# DDR-Memory.net
KiCad netlist of a schematic drawn in Altium Designer
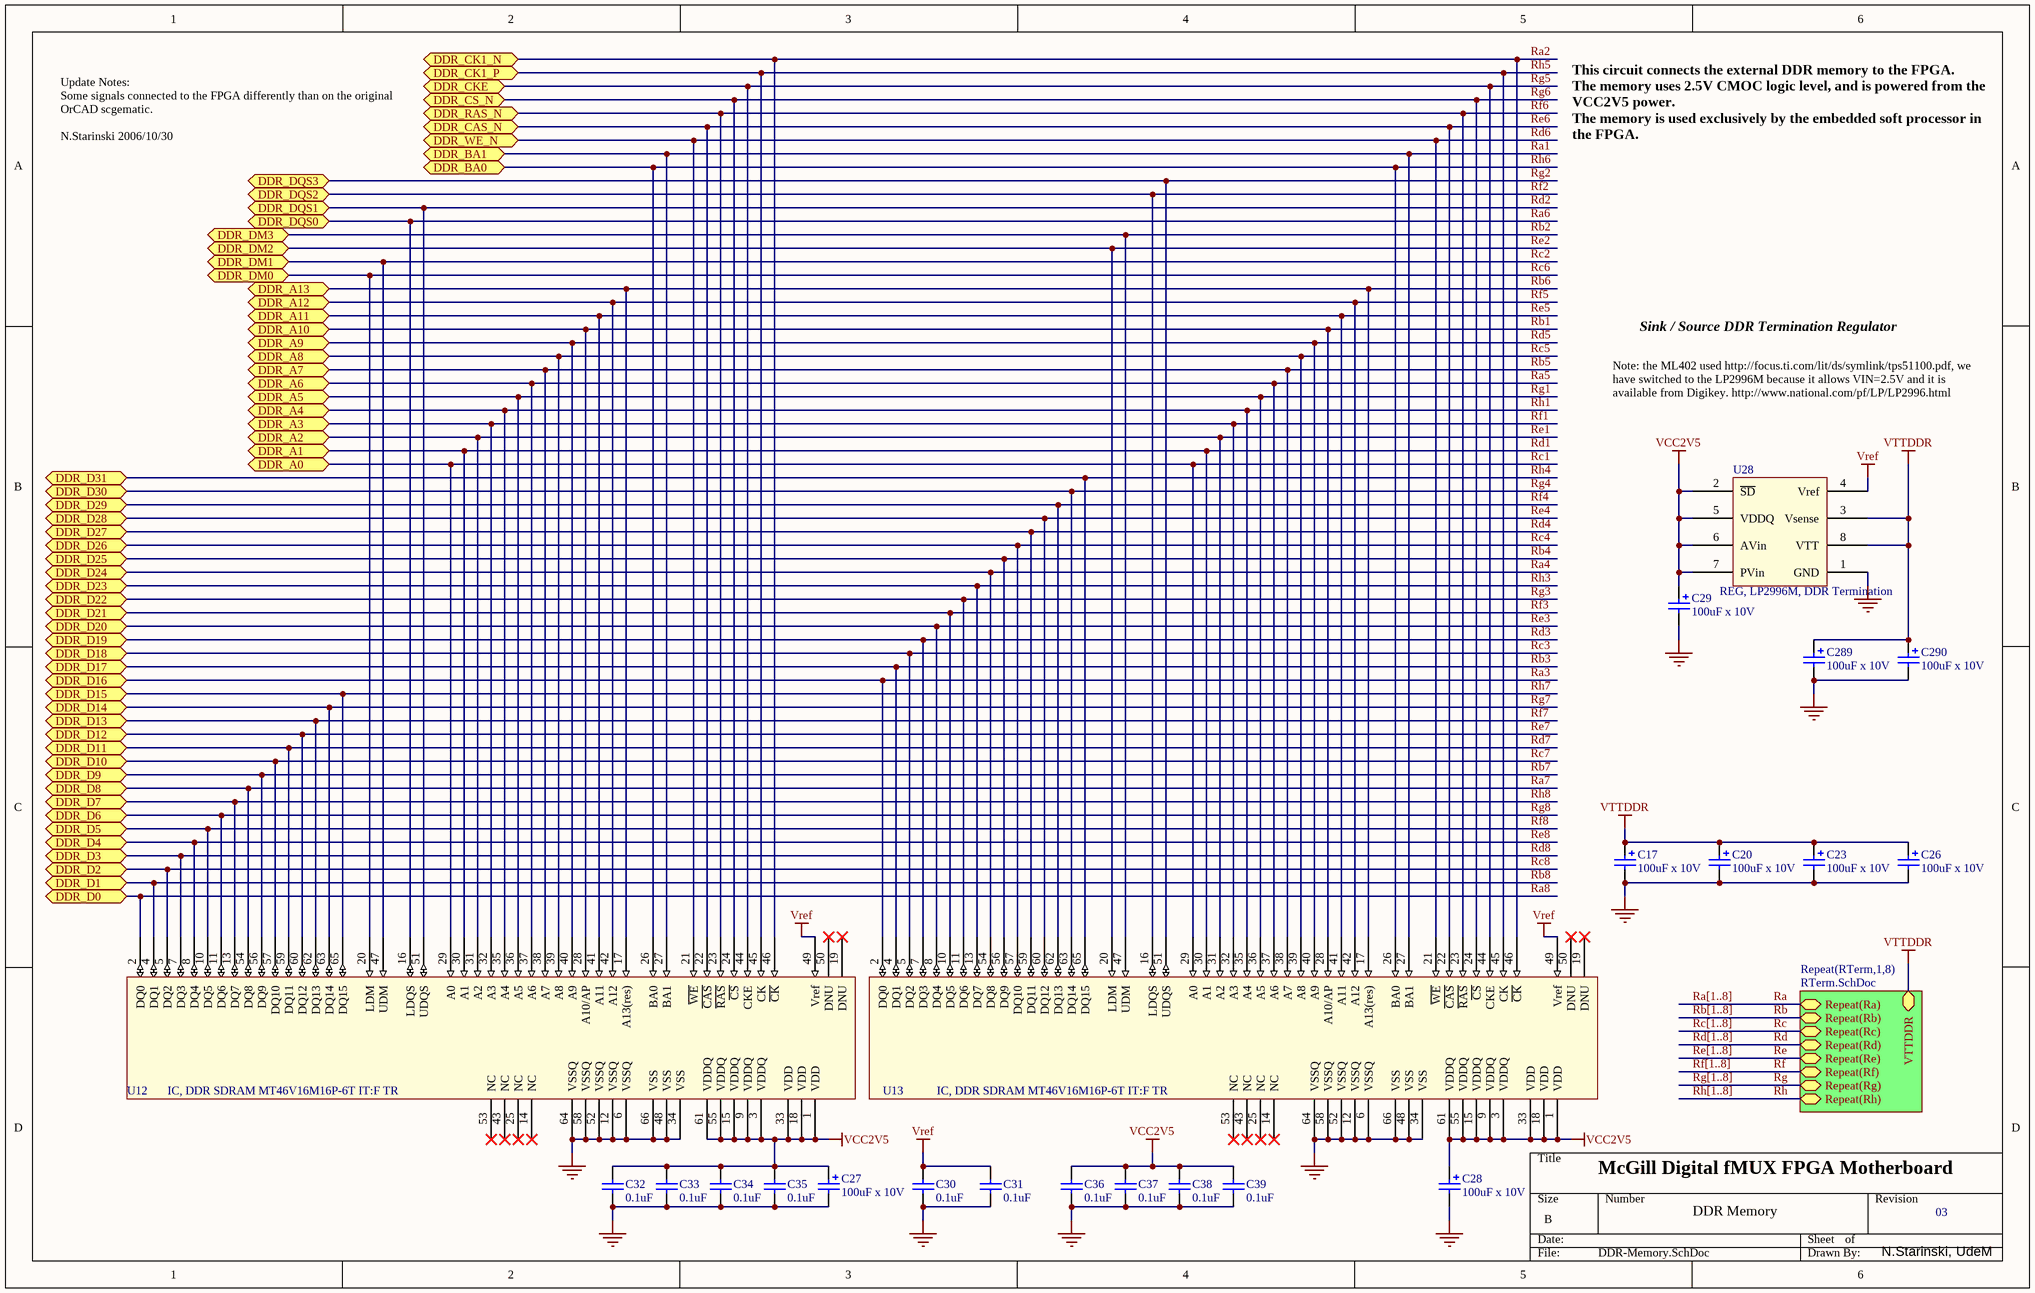
[diagram p0: DDR-Memory.SchDoc]

(export (version "E")
  (design (tool "Eeschema 10.0.6"))
  (components
    (comp (ref "C17")
      (value "100uF x 10V")
      (footprint "TC6032-2412")
      (description "CAP TANTC TPSC107K010R0075")
      (fields (field (name "PUBLISHER") "Altium Limited"))
      (libsource (lib "Miscellaneous Devices 02") (part "Cap Pol3"))
    )
    (comp (ref "C20")
      (value "100uF x 10V")
      (footprint "TC6032-2412")
      (description "CAP TANTC TPSC107K010R0075")
      (fields (field (name "PUBLISHER") "Altium Limited"))
      (libsource (lib "Miscellaneous Devices 02") (part "Cap Pol3"))
    )
    (comp (ref "C23")
      (value "100uF x 10V")
      (footprint "TC6032-2412")
      (description "CAP TANTC TPSC107K010R0075")
      (fields (field (name "PUBLISHER") "Altium Limited"))
      (libsource (lib "Miscellaneous Devices 02") (part "Cap Pol3"))
    )
    (comp (ref "C26")
      (value "100uF x 10V")
      (footprint "TC6032-2412")
      (description "CAP TANTC TPSC107K010R0075")
      (fields (field (name "PUBLISHER") "Altium Limited"))
      (libsource (lib "Miscellaneous Devices 02") (part "Cap Pol3"))
    )
    (comp (ref "C27")
      (value "100uF x 10V")
      (footprint "TC6032-2412")
      (description "CAP TANTC TPSC107K010R0075")
      (fields (field (name "PUBLISHER") "Altium Limited"))
      (libsource (lib "Miscellaneous Devices 02") (part "Cap Pol3"))
    )
    (comp (ref "C28")
      (value "100uF x 10V")
      (footprint "TC6032-2412")
      (description "CAP TANTC TPSC107K010R0075")
      (fields (field (name "PUBLISHER") "Altium Limited"))
      (libsource (lib "Miscellaneous Devices 02") (part "Cap Pol3"))
    )
    (comp (ref "C29")
      (value "100uF x 10V")
      (footprint "TC6032-2412")
      (description "CAP TANTC TPSC107K010R0075")
      (fields (field (name "PUBLISHER") "Altium Limited"))
      (libsource (lib "Miscellaneous Devices 02") (part "Cap Pol3"))
    )
    (comp (ref "C30")
      (value "0.1uF")
      (footprint "CC1608-0603")
      (description "Capacitor (Semiconductor SIM Model)")
      (fields (field (name "PUBLISHER") "Altium Limited"))
      (libsource (lib "Miscellaneous Devices 02") (part "Cap Semi"))
    )
    (comp (ref "C31")
      (value "0.1uF")
      (footprint "CC1608-0603")
      (description "Capacitor (Semiconductor SIM Model)")
      (fields (field (name "PUBLISHER") "Altium Limited"))
      (libsource (lib "Miscellaneous Devices 02") (part "Cap Semi"))
    )
    (comp (ref "C32")
      (value "0.1uF")
      (footprint "CC1608-0603")
      (description "Capacitor (Semiconductor SIM Model)")
      (fields (field (name "PUBLISHER") "Altium Limited"))
      (libsource (lib "Miscellaneous Devices 02") (part "Cap Semi"))
    )
    (comp (ref "C33")
      (value "0.1uF")
      (footprint "CC1608-0603")
      (description "Capacitor (Semiconductor SIM Model)")
      (fields (field (name "PUBLISHER") "Altium Limited"))
      (libsource (lib "Miscellaneous Devices 02") (part "Cap Semi"))
    )
    (comp (ref "C34")
      (value "0.1uF")
      (footprint "CC1608-0603")
      (description "Capacitor (Semiconductor SIM Model)")
      (fields (field (name "PUBLISHER") "Altium Limited"))
      (libsource (lib "Miscellaneous Devices 02") (part "Cap Semi"))
    )
    (comp (ref "C35")
      (value "0.1uF")
      (footprint "CC1608-0603")
      (description "Capacitor (Semiconductor SIM Model)")
      (fields (field (name "PUBLISHER") "Altium Limited"))
      (libsource (lib "Miscellaneous Devices 02") (part "Cap Semi"))
    )
    (comp (ref "C36")
      (value "0.1uF")
      (footprint "CC1608-0603")
      (description "Capacitor (Semiconductor SIM Model)")
      (fields (field (name "PUBLISHER") "Altium Limited"))
      (libsource (lib "Miscellaneous Devices 02") (part "Cap Semi"))
    )
    (comp (ref "C37")
      (value "0.1uF")
      (footprint "CC1608-0603")
      (description "Capacitor (Semiconductor SIM Model)")
      (fields (field (name "PUBLISHER") "Altium Limited"))
      (libsource (lib "Miscellaneous Devices 02") (part "Cap Semi"))
    )
    (comp (ref "C38")
      (value "0.1uF")
      (footprint "CC1608-0603")
      (description "Capacitor (Semiconductor SIM Model)")
      (fields (field (name "PUBLISHER") "Altium Limited"))
      (libsource (lib "Miscellaneous Devices 02") (part "Cap Semi"))
    )
    (comp (ref "C39")
      (value "0.1uF")
      (footprint "CC1608-0603")
      (description "Capacitor (Semiconductor SIM Model)")
      (fields (field (name "PUBLISHER") "Altium Limited"))
      (libsource (lib "Miscellaneous Devices 02") (part "Cap Semi"))
    )
    (comp (ref "C289")
      (value "100uF x 10V")
      (footprint "TC6032-2412")
      (description "CAP TANTC TPSC107K010R0075")
      (fields (field (name "PUBLISHER") "Altium Limited"))
      (libsource (lib "Miscellaneous Devices 02") (part "Cap Pol3"))
    )
    (comp (ref "C290")
      (value "100uF x 10V")
      (footprint "TC6032-2412")
      (description "CAP TANTC TPSC107K010R0075")
      (fields (field (name "PUBLISHER") "Altium Limited"))
      (libsource (lib "Miscellaneous Devices 02") (part "Cap Pol3"))
    )
    (comp (ref "U12")
      (value "IC, DDR SDRAM MT46V16M16P-6T IT:F TR")
      (footprint "TSOP-66")
      (description "256Mb, 4Meg X 16 X 4 banks DDR SDRAM")
      (libsource (lib "Micron Memory Dynamic RAM") (part "MT46V16M16"))
    )
    (comp (ref "U13")
      (value "IC, DDR SDRAM MT46V16M16P-6T IT:F TR")
      (footprint "TSOP-66")
      (description "256Mb, 4Meg X 16 X 4 banks DDR SDRAM")
      (libsource (lib "Micron Memory Dynamic RAM") (part "MT46V16M16"))
    )
    (comp (ref "U28")
      (value "REG, LP2996M, DDR Termination")
      (footprint "M08A")
      (description "DDR Termination Regulator")
      (libsource (lib "NSC Power Mgt Voltage Regulator") (part "LP2996"))
    )
  )
  (nets
    (net (code "3") (name "/Ra1") (class "Default")
      (node (ref "U12") (pin "27") (pinfunction "BA1_27") (pintype "input"))
      (node (ref "U13") (pin "27") (pinfunction "BA1_27") (pintype "input"))
    )
    (net (code "4") (name "/Ra2") (class "Default")
      (node (ref "U12") (pin "46") (pinfunction "~{CK}_46") (pintype "input"))
      (node (ref "U13") (pin "46") (pinfunction "~{CK}_46") (pintype "input"))
    )
    (net (code "5") (name "/Ra3") (class "Default")
      (node (ref "U13") (pin "2") (pinfunction "DQ0_2") (pintype "bidirectional"))
    )
    (net (code "6") (name "/Ra4") (class "Default")
      (node (ref "U13") (pin "54") (pinfunction "DQ8_54") (pintype "bidirectional"))
    )
    (net (code "7") (name "/Ra5") (class "Default")
      (node (ref "U12") (pin "37") (pinfunction "A6_37") (pintype "input"))
      (node (ref "U13") (pin "37") (pinfunction "A6_37") (pintype "input"))
    )
    (net (code "8") (name "/Ra6") (class "Default")
      (node (ref "U12") (pin "16") (pinfunction "LDQS_16") (pintype "bidirectional"))
    )
    (net (code "9") (name "/Ra7") (class "Default")
      (node (ref "U12") (pin "54") (pinfunction "DQ8_54") (pintype "bidirectional"))
    )
    (net (code "10") (name "/Ra8") (class "Default")
      (node (ref "U12") (pin "2") (pinfunction "DQ0_2") (pintype "bidirectional"))
    )
    (net (code "13") (name "/Rb1") (class "Default")
      (node (ref "U12") (pin "28") (pinfunction "A10/AP_28") (pintype "input"))
      (node (ref "U13") (pin "28") (pinfunction "A10/AP_28") (pintype "input"))
    )
    (net (code "14") (name "/Rb2") (class "Default")
      (node (ref "U13") (pin "47") (pinfunction "UDM_47") (pintype "input"))
    )
    (net (code "15") (name "/Rb3") (class "Default")
      (node (ref "U13") (pin "4") (pinfunction "DQ1_4") (pintype "bidirectional"))
    )
    (net (code "16") (name "/Rb4") (class "Default")
      (node (ref "U13") (pin "56") (pinfunction "DQ9_56") (pintype "bidirectional"))
    )
    (net (code "17") (name "/Rb5") (class "Default")
      (node (ref "U12") (pin "38") (pinfunction "A7_38") (pintype "input"))
      (node (ref "U13") (pin "38") (pinfunction "A7_38") (pintype "input"))
    )
    (net (code "18") (name "/Rb6") (class "Default")
      (node (ref "U12") (pin "17") (pinfunction "A13(res)_17") (pintype "input"))
      (node (ref "U13") (pin "17") (pinfunction "A13(res)_17") (pintype "input"))
    )
    (net (code "19") (name "/Rb7") (class "Default")
      (node (ref "U12") (pin "56") (pinfunction "DQ9_56") (pintype "bidirectional"))
    )
    (net (code "20") (name "/Rb8") (class "Default")
      (node (ref "U12") (pin "4") (pinfunction "DQ1_4") (pintype "bidirectional"))
    )
    (net (code "23") (name "/Rc1") (class "Default")
      (node (ref "U12") (pin "29") (pinfunction "A0_29") (pintype "input"))
      (node (ref "U13") (pin "29") (pinfunction "A0_29") (pintype "input"))
    )
    (net (code "24") (name "/Rc2") (class "Default")
      (node (ref "U12") (pin "47") (pinfunction "UDM_47") (pintype "input"))
    )
    (net (code "25") (name "/Rc3") (class "Default")
      (node (ref "U13") (pin "5") (pinfunction "DQ2_5") (pintype "bidirectional"))
    )
    (net (code "26") (name "/Rc4") (class "Default")
      (node (ref "U13") (pin "57") (pinfunction "DQ10_57") (pintype "bidirectional"))
    )
    (net (code "27") (name "/Rc5") (class "Default")
      (node (ref "U12") (pin "39") (pinfunction "A8_39") (pintype "input"))
      (node (ref "U13") (pin "39") (pinfunction "A8_39") (pintype "input"))
    )
    (net (code "28") (name "/Rc6") (class "Default")
      (node (ref "U12") (pin "20") (pinfunction "LDM_20") (pintype "input"))
    )
    (net (code "29") (name "/Rc7") (class "Default")
      (node (ref "U12") (pin "57") (pinfunction "DQ10_57") (pintype "bidirectional"))
    )
    (net (code "30") (name "/Rc8") (class "Default")
      (node (ref "U12") (pin "5") (pinfunction "DQ2_5") (pintype "bidirectional"))
    )
    (net (code "33") (name "/Rd1") (class "Default")
      (node (ref "U12") (pin "30") (pinfunction "A1_30") (pintype "input"))
      (node (ref "U13") (pin "30") (pinfunction "A1_30") (pintype "input"))
    )
    (net (code "34") (name "/Rd2") (class "Default")
      (node (ref "U12") (pin "51") (pinfunction "UDQS_51") (pintype "bidirectional"))
    )
    (net (code "35") (name "/Rd3") (class "Default")
      (node (ref "U13") (pin "7") (pinfunction "DQ3_7") (pintype "bidirectional"))
    )
    (net (code "36") (name "/Rd4") (class "Default")
      (node (ref "U13") (pin "59") (pinfunction "DQ11_59") (pintype "bidirectional"))
    )
    (net (code "37") (name "/Rd5") (class "Default")
      (node (ref "U12") (pin "40") (pinfunction "A9_40") (pintype "input"))
      (node (ref "U13") (pin "40") (pinfunction "A9_40") (pintype "input"))
    )
    (net (code "38") (name "/Rd6") (class "Default")
      (node (ref "U12") (pin "21") (pinfunction "~{WE}_21") (pintype "input"))
      (node (ref "U13") (pin "21") (pinfunction "~{WE}_21") (pintype "input"))
    )
    (net (code "39") (name "/Rd7") (class "Default")
      (node (ref "U12") (pin "59") (pinfunction "DQ11_59") (pintype "bidirectional"))
    )
    (net (code "40") (name "/Rd8") (class "Default")
      (node (ref "U12") (pin "7") (pinfunction "DQ3_7") (pintype "bidirectional"))
    )
    (net (code "43") (name "/Re1") (class "Default")
      (node (ref "U12") (pin "31") (pinfunction "A2_31") (pintype "input"))
      (node (ref "U13") (pin "31") (pinfunction "A2_31") (pintype "input"))
    )
    (net (code "44") (name "/Re2") (class "Default")
      (node (ref "U13") (pin "20") (pinfunction "LDM_20") (pintype "input"))
    )
    (net (code "45") (name "/Re3") (class "Default")
      (node (ref "U13") (pin "8") (pinfunction "DQ4_8") (pintype "bidirectional"))
    )
    (net (code "46") (name "/Re4") (class "Default")
      (node (ref "U13") (pin "60") (pinfunction "DQ12_60") (pintype "bidirectional"))
    )
    (net (code "47") (name "/Re5") (class "Default")
      (node (ref "U12") (pin "41") (pinfunction "A11_41") (pintype "input"))
      (node (ref "U13") (pin "41") (pinfunction "A11_41") (pintype "input"))
    )
    (net (code "48") (name "/Re6") (class "Default")
      (node (ref "U12") (pin "22") (pinfunction "~{CAS}_22") (pintype "input"))
      (node (ref "U13") (pin "22") (pinfunction "~{CAS}_22") (pintype "input"))
    )
    (net (code "49") (name "/Re7") (class "Default")
      (node (ref "U12") (pin "60") (pinfunction "DQ12_60") (pintype "bidirectional"))
    )
    (net (code "50") (name "/Re8") (class "Default")
      (node (ref "U12") (pin "8") (pinfunction "DQ4_8") (pintype "bidirectional"))
    )
    (net (code "53") (name "/Rf1") (class "Default")
      (node (ref "U12") (pin "32") (pinfunction "A3_32") (pintype "input"))
      (node (ref "U13") (pin "32") (pinfunction "A3_32") (pintype "input"))
    )
    (net (code "54") (name "/Rf2") (class "Default")
      (node (ref "U13") (pin "16") (pinfunction "LDQS_16") (pintype "bidirectional"))
    )
    (net (code "55") (name "/Rf3") (class "Default")
      (node (ref "U13") (pin "10") (pinfunction "DQ5_10") (pintype "bidirectional"))
    )
    (net (code "56") (name "/Rf4") (class "Default")
      (node (ref "U13") (pin "62") (pinfunction "DQ13_62") (pintype "bidirectional"))
    )
    (net (code "57") (name "/Rf5") (class "Default")
      (node (ref "U12") (pin "42") (pinfunction "A12_42") (pintype "input"))
      (node (ref "U13") (pin "42") (pinfunction "A12_42") (pintype "input"))
    )
    (net (code "58") (name "/Rf6") (class "Default")
      (node (ref "U12") (pin "23") (pinfunction "~{RAS}_23") (pintype "input"))
      (node (ref "U13") (pin "23") (pinfunction "~{RAS}_23") (pintype "input"))
    )
    (net (code "59") (name "/Rf7") (class "Default")
      (node (ref "U12") (pin "62") (pinfunction "DQ13_62") (pintype "bidirectional"))
    )
    (net (code "60") (name "/Rf8") (class "Default")
      (node (ref "U12") (pin "10") (pinfunction "DQ5_10") (pintype "bidirectional"))
    )
    (net (code "63") (name "/Rg1") (class "Default")
      (node (ref "U12") (pin "36") (pinfunction "A5_36") (pintype "input"))
      (node (ref "U13") (pin "36") (pinfunction "A5_36") (pintype "input"))
    )
    (net (code "64") (name "/Rg2") (class "Default")
      (node (ref "U13") (pin "51") (pinfunction "UDQS_51") (pintype "bidirectional"))
    )
    (net (code "65") (name "/Rg3") (class "Default")
      (node (ref "U13") (pin "11") (pinfunction "DQ6_11") (pintype "bidirectional"))
    )
    (net (code "66") (name "/Rg4") (class "Default")
      (node (ref "U13") (pin "63") (pinfunction "DQ14_63") (pintype "bidirectional"))
    )
    (net (code "67") (name "/Rg5") (class "Default")
      (node (ref "U12") (pin "44") (pinfunction "CKE_44") (pintype "input"))
      (node (ref "U13") (pin "44") (pinfunction "CKE_44") (pintype "input"))
    )
    (net (code "68") (name "/Rg6") (class "Default")
      (node (ref "U12") (pin "24") (pinfunction "~{CS}_24") (pintype "input"))
      (node (ref "U13") (pin "24") (pinfunction "~{CS}_24") (pintype "input"))
    )
    (net (code "69") (name "/Rg7") (class "Default")
      (node (ref "U12") (pin "63") (pinfunction "DQ14_63") (pintype "bidirectional"))
    )
    (net (code "70") (name "/Rg8") (class "Default")
      (node (ref "U12") (pin "11") (pinfunction "DQ6_11") (pintype "bidirectional"))
    )
    (net (code "73") (name "/Rh1") (class "Default")
      (node (ref "U12") (pin "35") (pinfunction "A4_35") (pintype "input"))
      (node (ref "U13") (pin "35") (pinfunction "A4_35") (pintype "input"))
    )
    (net (code "74") (name "/Rh3") (class "Default")
      (node (ref "U13") (pin "13") (pinfunction "DQ7_13") (pintype "bidirectional"))
    )
    (net (code "75") (name "/Rh4") (class "Default")
      (node (ref "U13") (pin "65") (pinfunction "DQ15_65") (pintype "bidirectional"))
    )
    (net (code "76") (name "/Rh5") (class "Default")
      (node (ref "U12") (pin "45") (pinfunction "CK_45") (pintype "input"))
      (node (ref "U13") (pin "45") (pinfunction "CK_45") (pintype "input"))
    )
    (net (code "77") (name "/Rh6") (class "Default")
      (node (ref "U12") (pin "26") (pinfunction "BA0_26") (pintype "input"))
      (node (ref "U13") (pin "26") (pinfunction "BA0_26") (pintype "input"))
    )
    (net (code "78") (name "/Rh7") (class "Default")
      (node (ref "U12") (pin "65") (pinfunction "DQ15_65") (pintype "bidirectional"))
    )
    (net (code "79") (name "/Rh8") (class "Default")
      (node (ref "U12") (pin "13") (pinfunction "DQ7_13") (pintype "bidirectional"))
    )
    (net (code "81") (name "GND") (class "Default")
      (node (ref "C17") (pin "2") (pinfunction "2_2") (pintype "passive"))
      (node (ref "C20") (pin "2") (pinfunction "2_2") (pintype "passive"))
      (node (ref "C23") (pin "2") (pinfunction "2_2") (pintype "passive"))
      (node (ref "C26") (pin "2") (pinfunction "2_2") (pintype "passive"))
      (node (ref "C27") (pin "2") (pinfunction "2_2") (pintype "passive"))
      (node (ref "C28") (pin "2") (pinfunction "2_2") (pintype "passive"))
      (node (ref "C289") (pin "2") (pinfunction "2_2") (pintype "passive"))
      (node (ref "C29") (pin "2") (pinfunction "2_2") (pintype "passive"))
      (node (ref "C290") (pin "2") (pinfunction "2_2") (pintype "passive"))
      (node (ref "C30") (pin "1") (pinfunction "1_1") (pintype "passive"))
      (node (ref "C31") (pin "1") (pinfunction "1_1") (pintype "passive"))
      (node (ref "C32") (pin "1") (pinfunction "1_1") (pintype "passive"))
      (node (ref "C33") (pin "1") (pinfunction "1_1") (pintype "passive"))
      (node (ref "C34") (pin "1") (pinfunction "1_1") (pintype "passive"))
      (node (ref "C35") (pin "1") (pinfunction "1_1") (pintype "passive"))
      (node (ref "C36") (pin "1") (pinfunction "1_1") (pintype "passive"))
      (node (ref "C37") (pin "1") (pinfunction "1_1") (pintype "passive"))
      (node (ref "C38") (pin "1") (pinfunction "1_1") (pintype "passive"))
      (node (ref "C39") (pin "1") (pinfunction "1_1") (pintype "passive"))
      (node (ref "U12") (pin "12") (pinfunction "VSSQ_12") (pintype "power_in"))
      (node (ref "U12") (pin "34") (pinfunction "VSS_34") (pintype "power_in"))
      (node (ref "U12") (pin "48") (pinfunction "VSS_48") (pintype "power_in"))
      (node (ref "U12") (pin "52") (pinfunction "VSSQ_52") (pintype "power_in"))
      (node (ref "U12") (pin "58") (pinfunction "VSSQ_58") (pintype "power_in"))
      (node (ref "U12") (pin "6") (pinfunction "VSSQ_6") (pintype "power_in"))
      (node (ref "U12") (pin "64") (pinfunction "VSSQ_64") (pintype "power_in"))
      (node (ref "U12") (pin "66") (pinfunction "VSS_66") (pintype "power_in"))
      (node (ref "U13") (pin "12") (pinfunction "VSSQ_12") (pintype "power_in"))
      (node (ref "U13") (pin "34") (pinfunction "VSS_34") (pintype "power_in"))
      (node (ref "U13") (pin "48") (pinfunction "VSS_48") (pintype "power_in"))
      (node (ref "U13") (pin "52") (pinfunction "VSSQ_52") (pintype "power_in"))
      (node (ref "U13") (pin "58") (pinfunction "VSSQ_58") (pintype "power_in"))
      (node (ref "U13") (pin "6") (pinfunction "VSSQ_6") (pintype "power_in"))
      (node (ref "U13") (pin "64") (pinfunction "VSSQ_64") (pintype "power_in"))
      (node (ref "U13") (pin "66") (pinfunction "VSS_66") (pintype "power_in"))
      (node (ref "U28") (pin "1") (pinfunction "GND_1") (pintype "power_in"))
    )
    (net (code "82") (name "VCC2V5") (class "Default")
      (node (ref "C27") (pin "1") (pinfunction "1_1") (pintype "passive"))
      (node (ref "C28") (pin "1") (pinfunction "1_1") (pintype "passive"))
      (node (ref "C29") (pin "1") (pinfunction "1_1") (pintype "passive"))
      (node (ref "C32") (pin "2") (pinfunction "2_2") (pintype "passive"))
      (node (ref "C33") (pin "2") (pinfunction "2_2") (pintype "passive"))
      (node (ref "C34") (pin "2") (pinfunction "2_2") (pintype "passive"))
      (node (ref "C35") (pin "2") (pinfunction "2_2") (pintype "passive"))
      (node (ref "C36") (pin "2") (pinfunction "2_2") (pintype "passive"))
      (node (ref "C37") (pin "2") (pinfunction "2_2") (pintype "passive"))
      (node (ref "C38") (pin "2") (pinfunction "2_2") (pintype "passive"))
      (node (ref "C39") (pin "2") (pinfunction "2_2") (pintype "passive"))
      (node (ref "U12") (pin "1") (pinfunction "VDD_1") (pintype "power_in"))
      (node (ref "U12") (pin "15") (pinfunction "VDDQ_15") (pintype "power_in"))
      (node (ref "U12") (pin "18") (pinfunction "VDD_18") (pintype "power_in"))
      (node (ref "U12") (pin "3") (pinfunction "VDDQ_3") (pintype "power_in"))
      (node (ref "U12") (pin "33") (pinfunction "VDD_33") (pintype "power_in"))
      (node (ref "U12") (pin "55") (pinfunction "VDDQ_55") (pintype "power_in"))
      (node (ref "U12") (pin "61") (pinfunction "VDDQ_61") (pintype "power_in"))
      (node (ref "U12") (pin "9") (pinfunction "VDDQ_9") (pintype "power_in"))
      (node (ref "U13") (pin "1") (pinfunction "VDD_1") (pintype "power_in"))
      (node (ref "U13") (pin "15") (pinfunction "VDDQ_15") (pintype "power_in"))
      (node (ref "U13") (pin "18") (pinfunction "VDD_18") (pintype "power_in"))
      (node (ref "U13") (pin "3") (pinfunction "VDDQ_3") (pintype "power_in"))
      (node (ref "U13") (pin "33") (pinfunction "VDD_33") (pintype "power_in"))
      (node (ref "U13") (pin "55") (pinfunction "VDDQ_55") (pintype "power_in"))
      (node (ref "U13") (pin "61") (pinfunction "VDDQ_61") (pintype "power_in"))
      (node (ref "U13") (pin "9") (pinfunction "VDDQ_9") (pintype "power_in"))
      (node (ref "U28") (pin "2") (pinfunction "~{SD}_2") (pintype "passive"))
      (node (ref "U28") (pin "5") (pinfunction "VDDQ_5") (pintype "passive"))
      (node (ref "U28") (pin "6") (pinfunction "AVin_6") (pintype "passive"))
      (node (ref "U28") (pin "7") (pinfunction "PVin_7") (pintype "passive"))
    )
    (net (code "83") (name "VTTDDR") (class "Default")
      (node (ref "C17") (pin "1") (pinfunction "1_1") (pintype "passive"))
      (node (ref "C20") (pin "1") (pinfunction "1_1") (pintype "passive"))
      (node (ref "C23") (pin "1") (pinfunction "1_1") (pintype "passive"))
      (node (ref "C26") (pin "1") (pinfunction "1_1") (pintype "passive"))
      (node (ref "C289") (pin "1") (pinfunction "1_1") (pintype "passive"))
      (node (ref "C290") (pin "1") (pinfunction "1_1") (pintype "passive"))
      (node (ref "U28") (pin "3") (pinfunction "Vsense_3") (pintype "passive"))
      (node (ref "U28") (pin "8") (pinfunction "VTT_8") (pintype "passive"))
    )
    (net (code "84") (name "Vref") (class "Default")
      (node (ref "C30") (pin "2") (pinfunction "2_2") (pintype "passive"))
      (node (ref "C31") (pin "2") (pinfunction "2_2") (pintype "passive"))
      (node (ref "U12") (pin "49") (pinfunction "Vref_49") (pintype "input"))
      (node (ref "U13") (pin "49") (pinfunction "Vref_49") (pintype "input"))
      (node (ref "U28") (pin "4") (pinfunction "Vref_4") (pintype "passive"))
    )
    (net (code "85") (name "unconnected-(U12-DNU-Pad19)") (class "Default")
      (node (ref "U12") (pin "19") (pinfunction "DNU_19") (pintype "passive+no_connect"))
    )
    (net (code "86") (name "unconnected-(U12-DNU-Pad50)") (class "Default")
      (node (ref "U12") (pin "50") (pinfunction "DNU_50") (pintype "passive+no_connect"))
    )
    (net (code "87") (name "unconnected-(U12-NC-Pad14)") (class "Default")
      (node (ref "U12") (pin "14") (pinfunction "NC_14") (pintype "passive+no_connect"))
    )
    (net (code "88") (name "unconnected-(U12-NC-Pad25)") (class "Default")
      (node (ref "U12") (pin "25") (pinfunction "NC_25") (pintype "passive+no_connect"))
    )
    (net (code "89") (name "unconnected-(U12-NC-Pad43)") (class "Default")
      (node (ref "U12") (pin "43") (pinfunction "NC_43") (pintype "passive+no_connect"))
    )
    (net (code "90") (name "unconnected-(U12-NC-Pad53)") (class "Default")
      (node (ref "U12") (pin "53") (pinfunction "NC_53") (pintype "passive+no_connect"))
    )
    (net (code "91") (name "unconnected-(U13-DNU-Pad19)") (class "Default")
      (node (ref "U13") (pin "19") (pinfunction "DNU_19") (pintype "passive+no_connect"))
    )
    (net (code "92") (name "unconnected-(U13-DNU-Pad50)") (class "Default")
      (node (ref "U13") (pin "50") (pinfunction "DNU_50") (pintype "passive+no_connect"))
    )
    (net (code "93") (name "unconnected-(U13-NC-Pad14)") (class "Default")
      (node (ref "U13") (pin "14") (pinfunction "NC_14") (pintype "passive+no_connect"))
    )
    (net (code "94") (name "unconnected-(U13-NC-Pad25)") (class "Default")
      (node (ref "U13") (pin "25") (pinfunction "NC_25") (pintype "passive+no_connect"))
    )
    (net (code "95") (name "unconnected-(U13-NC-Pad43)") (class "Default")
      (node (ref "U13") (pin "43") (pinfunction "NC_43") (pintype "passive+no_connect"))
    )
    (net (code "96") (name "unconnected-(U13-NC-Pad53)") (class "Default")
      (node (ref "U13") (pin "53") (pinfunction "NC_53") (pintype "passive+no_connect"))
    )
  )
)
